# sensor_modul.net
KiCad netlist of a schematic drawn in EAGLE
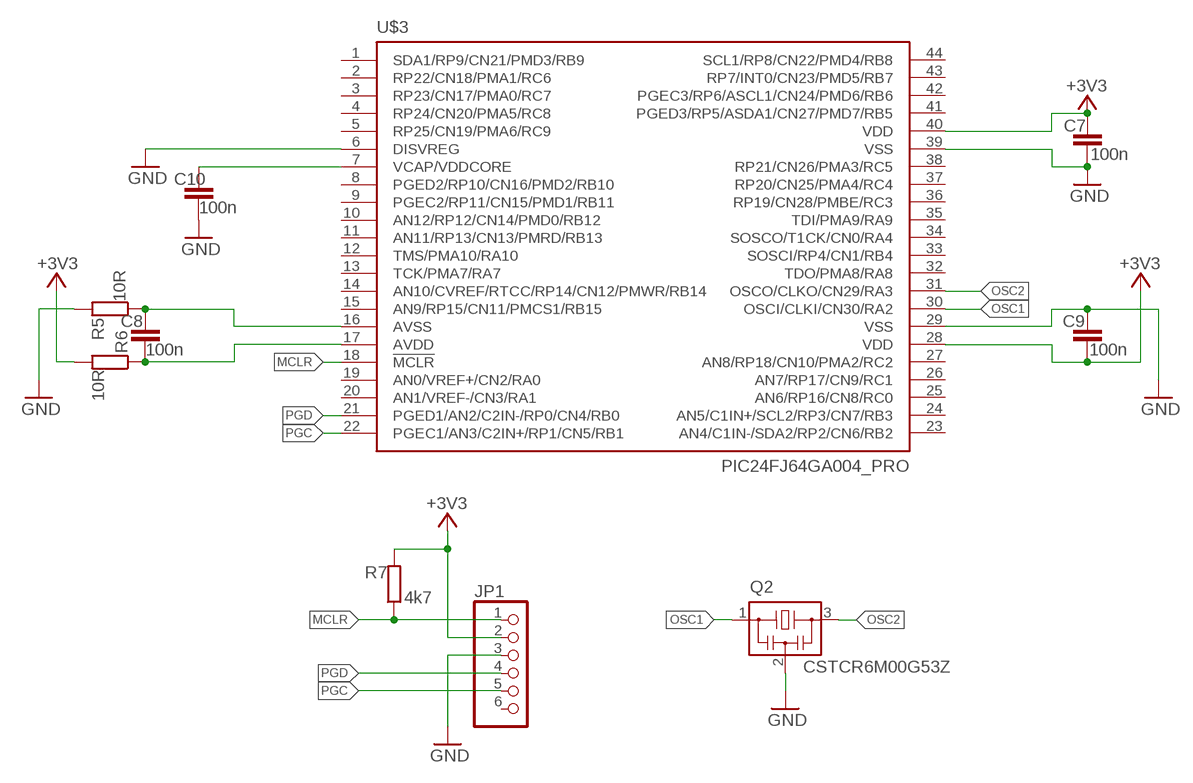
[diagram p0: schematic, sheet 1]

(export (version "E")
  (design (tool "Eeschema 10.0.6"))
  (components
    (comp (ref "C7")
      (value "100n")
      (footprint "eagle-import:C1206K")
      (libsource (lib "eagle-import") (part "C-EUC1206K"))
    )
    (comp (ref "C8")
      (value "100n")
      (footprint "eagle-import:C1206K")
      (libsource (lib "eagle-import") (part "C-EUC1206K"))
    )
    (comp (ref "C9")
      (value "100n")
      (footprint "eagle-import:C1206K")
      (libsource (lib "eagle-import") (part "C-EUC1206K"))
    )
    (comp (ref "C10")
      (value "100n")
      (footprint "eagle-import:C1206K")
      (libsource (lib "eagle-import") (part "C-EUC1206K"))
    )
    (comp (ref "JP1")
      (value "PINHD-1X6")
      (footprint "eagle-import:1X06")
      (libsource (lib "eagle-import") (part "PINHD-1X6"))
    )
    (comp (ref "Q2")
      (value "CSTCR6M00G53Z")
      (footprint "eagle-import:CSTER12M")
      (fields (field (name "MPN") "CSTCC12M0"))
      (libsource (lib "eagle-import") (part "CSTCR6M00G53Z"))
    )
    (comp (ref "R5")
      (value "10R")
      (footprint "eagle-import:M1206")
      (libsource (lib "eagle-import") (part "R-EU_M1206"))
    )
    (comp (ref "R6")
      (value "10R")
      (footprint "eagle-import:M1206")
      (libsource (lib "eagle-import") (part "R-EU_M1206"))
    )
    (comp (ref "R7")
      (value "4k7")
      (footprint "eagle-import:M1206")
      (libsource (lib "eagle-import") (part "R-EU_M1206"))
    )
    (comp (ref "U$3")
      (value "PIC24FJ64GA004_PRO")
      (footprint "eagle-import:TQFP44")
      (libsource (lib "eagle-import") (part "PIC24FJ64GA004_PRO"))
    )
  )
  (nets
    (net (code "1") (name "+3V3") (class "Default")
      (node (ref "C7") (pin "2") (pinfunction "2_2") (pintype "passive"))
      (node (ref "C9") (pin "2") (pinfunction "2_2") (pintype "passive"))
      (node (ref "JP1") (pin "2") (pinfunction "2_2") (pintype "passive"))
      (node (ref "R6") (pin "2") (pinfunction "2_2") (pintype "passive"))
      (node (ref "R7") (pin "2") (pinfunction "2_2") (pintype "passive"))
      (node (ref "U$3") (pin "28") (pinfunction "VDD_28") (pintype "power_in"))
      (node (ref "U$3") (pin "40") (pinfunction "VDD_40") (pintype "power_in"))
    )
    (net (code "2") (name "GND") (class "Default")
      (node (ref "C10") (pin "2") (pinfunction "2_2") (pintype "passive"))
      (node (ref "C7") (pin "1") (pinfunction "1_1") (pintype "passive"))
      (node (ref "C9") (pin "1") (pinfunction "1_1") (pintype "passive"))
      (node (ref "JP1") (pin "3") (pinfunction "3_3") (pintype "passive"))
      (node (ref "Q2") (pin "2") (pinfunction "2_2") (pintype "passive"))
      (node (ref "R5") (pin "2") (pinfunction "2_2") (pintype "passive"))
      (node (ref "U$3") (pin "29") (pinfunction "VSS_29") (pintype "power_in"))
      (node (ref "U$3") (pin "39") (pinfunction "VSS_39") (pintype "power_in"))
      (node (ref "U$3") (pin "6") (pinfunction "DISVREG_6") (pintype "passive"))
    )
    (net (code "3") (name "MCLR") (class "Default")
      (node (ref "JP1") (pin "1") (pinfunction "1_1") (pintype "passive"))
      (node (ref "R7") (pin "1") (pinfunction "1_1") (pintype "passive"))
      (node (ref "U$3") (pin "18") (pinfunction "~{MCLR}_18") (pintype "bidirectional"))
    )
    (net (code "4") (name "Net-(U$3-AVDD)") (class "Default")
      (node (ref "C8") (pin "2") (pinfunction "2_2") (pintype "passive"))
      (node (ref "R6") (pin "1") (pinfunction "1_1") (pintype "passive"))
      (node (ref "U$3") (pin "17") (pinfunction "AVDD_17") (pintype "power_in"))
    )
    (net (code "5") (name "Net-(U$3-AVSS)") (class "Default")
      (node (ref "C8") (pin "1") (pinfunction "1_1") (pintype "passive"))
      (node (ref "R5") (pin "1") (pinfunction "1_1") (pintype "passive"))
      (node (ref "U$3") (pin "16") (pinfunction "AVSS_16") (pintype "power_in"))
    )
    (net (code "6") (name "Net-(U$3-VCAP{slash}VDDCORE)") (class "Default")
      (node (ref "C10") (pin "1") (pinfunction "1_1") (pintype "passive"))
      (node (ref "U$3") (pin "7") (pinfunction "VCAP/VDDCORE_7") (pintype "power_in"))
    )
    (net (code "7") (name "OSC1") (class "Default")
      (node (ref "Q2") (pin "1") (pinfunction "1_1") (pintype "passive"))
      (node (ref "U$3") (pin "30") (pinfunction "OSCI/CLKI/CN30/RA2_30") (pintype "bidirectional"))
    )
    (net (code "8") (name "OSC2") (class "Default")
      (node (ref "Q2") (pin "3") (pinfunction "3_3") (pintype "passive"))
      (node (ref "U$3") (pin "31") (pinfunction "OSCO/CLKO/CN29/RA3_31") (pintype "bidirectional"))
    )
    (net (code "9") (name "PGC") (class "Default")
      (node (ref "JP1") (pin "5") (pinfunction "5_5") (pintype "passive"))
      (node (ref "U$3") (pin "22") (pinfunction "PGEC1/AN3/C2IN+/RP1/CN5/RB1_22") (pintype "bidirectional"))
    )
    (net (code "10") (name "PGD") (class "Default")
      (node (ref "JP1") (pin "4") (pinfunction "4_4") (pintype "passive"))
      (node (ref "U$3") (pin "21") (pinfunction "PGED1/AN2/C2IN-/RP0/CN4/RB0_21") (pintype "bidirectional"))
    )
    (net (code "11") (name "unconnected-(JP1-Pad6)") (class "Default")
      (node (ref "JP1") (pin "6") (pinfunction "6_6") (pintype "passive"))
    )
    (net (code "12") (name "unconnected-(U$3-AN0{slash}VREF+{slash}CN2{slash}RA0-Pad19)") (class "Default")
      (node (ref "U$3") (pin "19") (pinfunction "AN0/VREF+/CN2/RA0_19") (pintype "bidirectional"))
    )
    (net (code "13") (name "unconnected-(U$3-AN1{slash}VREF-{slash}CN3{slash}RA1-Pad20)") (class "Default")
      (node (ref "U$3") (pin "20") (pinfunction "AN1/VREF-/CN3/RA1_20") (pintype "bidirectional"))
    )
    (net (code "14") (name "unconnected-(U$3-AN4{slash}C1IN-{slash}SDA2{slash}RP2{slash}CN6{slash}RB2-Pad23)") (class "Default")
      (node (ref "U$3") (pin "23") (pinfunction "AN4/C1IN-/SDA2/RP2/CN6/RB2_23") (pintype "bidirectional"))
    )
    (net (code "15") (name "unconnected-(U$3-AN5{slash}C1IN+{slash}SCL2{slash}RP3{slash}CN7{slash}RB3-Pad24)") (class "Default")
      (node (ref "U$3") (pin "24") (pinfunction "AN5/C1IN+/SCL2/RP3/CN7/RB3_24") (pintype "bidirectional"))
    )
    (net (code "16") (name "unconnected-(U$3-AN6{slash}RP16{slash}CN8{slash}RC0-Pad25)") (class "Default")
      (node (ref "U$3") (pin "25") (pinfunction "AN6/RP16/CN8/RC0_25") (pintype "bidirectional"))
    )
    (net (code "17") (name "unconnected-(U$3-AN7{slash}RP17{slash}CN9{slash}RC1-Pad26)") (class "Default")
      (node (ref "U$3") (pin "26") (pinfunction "AN7/RP17/CN9/RC1_26") (pintype "bidirectional"))
    )
    (net (code "18") (name "unconnected-(U$3-AN8{slash}RP18{slash}CN10{slash}PMA2{slash}RC2-Pad27)") (class "Default")
      (node (ref "U$3") (pin "27") (pinfunction "AN8/RP18/CN10/PMA2/RC2_27") (pintype "bidirectional"))
    )
    (net (code "19") (name "unconnected-(U$3-AN9{slash}RP15{slash}CN11{slash}PMCS1{slash}RB15-Pad15)") (class "Default")
      (node (ref "U$3") (pin "15") (pinfunction "AN9/RP15/CN11/PMCS1/RB15_15") (pintype "bidirectional"))
    )
    (net (code "20") (name "unconnected-(U$3-AN10{slash}CVREF{slash}RTCC{slash}RP14{slash}CN12{slash}PMWR{slash}RB14-Pad14)") (class "Default")
      (node (ref "U$3") (pin "14") (pinfunction "AN10/CVREF/RTCC/RP14/CN12/PMWR/RB14_14") (pintype "bidirectional"))
    )
    (net (code "21") (name "unconnected-(U$3-AN11{slash}RP13{slash}CN13{slash}PMRD{slash}RB13-Pad11)") (class "Default")
      (node (ref "U$3") (pin "11") (pinfunction "AN11/RP13/CN13/PMRD/RB13_11") (pintype "bidirectional"))
    )
    (net (code "22") (name "unconnected-(U$3-AN12{slash}RP12{slash}CN14{slash}PMD0{slash}RB12-Pad10)") (class "Default")
      (node (ref "U$3") (pin "10") (pinfunction "AN12/RP12/CN14/PMD0/RB12_10") (pintype "bidirectional"))
    )
    (net (code "23") (name "unconnected-(U$3-PGEC2{slash}RP11{slash}CN15{slash}PMD1{slash}RB11-Pad9)") (class "Default")
      (node (ref "U$3") (pin "9") (pinfunction "PGEC2/RP11/CN15/PMD1/RB11_9") (pintype "bidirectional"))
    )
    (net (code "24") (name "unconnected-(U$3-PGEC3{slash}RP6{slash}ASCL1{slash}CN24{slash}PMD6{slash}RB6-Pad42)") (class "Default")
      (node (ref "U$3") (pin "42") (pinfunction "PGEC3/RP6/ASCL1/CN24/PMD6/RB6_42") (pintype "bidirectional"))
    )
    (net (code "25") (name "unconnected-(U$3-PGED2{slash}RP10{slash}CN16{slash}PMD2{slash}RB10-Pad8)") (class "Default")
      (node (ref "U$3") (pin "8") (pinfunction "PGED2/RP10/CN16/PMD2/RB10_8") (pintype "bidirectional"))
    )
    (net (code "26") (name "unconnected-(U$3-PGED3{slash}RP5{slash}ASDA1{slash}CN27{slash}PMD7{slash}RB5-Pad41)") (class "Default")
      (node (ref "U$3") (pin "41") (pinfunction "PGED3/RP5/ASDA1/CN27/PMD7/RB5_41") (pintype "bidirectional"))
    )
    (net (code "27") (name "unconnected-(U$3-RP7{slash}INT0{slash}CN23{slash}PMD5{slash}RB7-Pad43)") (class "Default")
      (node (ref "U$3") (pin "43") (pinfunction "RP7/INT0/CN23/PMD5/RB7_43") (pintype "bidirectional"))
    )
    (net (code "28") (name "unconnected-(U$3-RP19{slash}CN28{slash}PMBE{slash}RC3-Pad36)") (class "Default")
      (node (ref "U$3") (pin "36") (pinfunction "RP19/CN28/PMBE/RC3_36") (pintype "bidirectional"))
    )
    (net (code "29") (name "unconnected-(U$3-RP20{slash}CN25{slash}PMA4{slash}RC4-Pad37)") (class "Default")
      (node (ref "U$3") (pin "37") (pinfunction "RP20/CN25/PMA4/RC4_37") (pintype "bidirectional"))
    )
    (net (code "30") (name "unconnected-(U$3-RP21{slash}CN26{slash}PMA3{slash}RC5-Pad38)") (class "Default")
      (node (ref "U$3") (pin "38") (pinfunction "RP21/CN26/PMA3/RC5_38") (pintype "bidirectional"))
    )
    (net (code "31") (name "unconnected-(U$3-RP22{slash}CN18{slash}PMA1{slash}RC6-Pad2)") (class "Default")
      (node (ref "U$3") (pin "2") (pinfunction "RP22/CN18/PMA1/RC6_2") (pintype "bidirectional"))
    )
    (net (code "32") (name "unconnected-(U$3-RP23{slash}CN17{slash}PMA0{slash}RC7-Pad3)") (class "Default")
      (node (ref "U$3") (pin "3") (pinfunction "RP23/CN17/PMA0/RC7_3") (pintype "bidirectional"))
    )
    (net (code "33") (name "unconnected-(U$3-RP24{slash}CN20{slash}PMA5{slash}RC8-Pad4)") (class "Default")
      (node (ref "U$3") (pin "4") (pinfunction "RP24/CN20/PMA5/RC8_4") (pintype "bidirectional"))
    )
    (net (code "34") (name "unconnected-(U$3-RP25{slash}CN19{slash}PMA6{slash}RC9-Pad5)") (class "Default")
      (node (ref "U$3") (pin "5") (pinfunction "RP25/CN19/PMA6/RC9_5") (pintype "bidirectional"))
    )
    (net (code "35") (name "unconnected-(U$3-SCL1{slash}RP8{slash}CN22{slash}PMD4{slash}RB8-Pad44)") (class "Default")
      (node (ref "U$3") (pin "44") (pinfunction "SCL1/RP8/CN22/PMD4/RB8_44") (pintype "bidirectional"))
    )
    (net (code "36") (name "unconnected-(U$3-SDA1{slash}RP9{slash}CN21{slash}PMD3{slash}RB9-Pad1)") (class "Default")
      (node (ref "U$3") (pin "1") (pinfunction "SDA1/RP9/CN21/PMD3/RB9_1") (pintype "bidirectional"))
    )
    (net (code "37") (name "unconnected-(U$3-SOSCI{slash}RP4{slash}CN1{slash}RB4-Pad33)") (class "Default")
      (node (ref "U$3") (pin "33") (pinfunction "SOSCI/RP4/CN1/RB4_33") (pintype "bidirectional"))
    )
    (net (code "38") (name "unconnected-(U$3-SOSCO{slash}T1CK{slash}CN0{slash}RA4-Pad34)") (class "Default")
      (node (ref "U$3") (pin "34") (pinfunction "SOSCO/T1CK/CN0/RA4_34") (pintype "bidirectional"))
    )
    (net (code "39") (name "unconnected-(U$3-TCK{slash}PMA7{slash}RA7-Pad13)") (class "Default")
      (node (ref "U$3") (pin "13") (pinfunction "TCK/PMA7/RA7_13") (pintype "input"))
    )
    (net (code "40") (name "unconnected-(U$3-TDI{slash}PMA9{slash}RA9-Pad35)") (class "Default")
      (node (ref "U$3") (pin "35") (pinfunction "TDI/PMA9/RA9_35") (pintype "input"))
    )
    (net (code "41") (name "unconnected-(U$3-TDO{slash}PMA8{slash}RA8-Pad32)") (class "Default")
      (node (ref "U$3") (pin "32") (pinfunction "TDO/PMA8/RA8_32") (pintype "output"))
    )
    (net (code "42") (name "unconnected-(U$3-TMS{slash}PMA10{slash}RA10-Pad12)") (class "Default")
      (node (ref "U$3") (pin "12") (pinfunction "TMS/PMA10/RA10_12") (pintype "input"))
    )
  )
)
